# BMS_Carrier_-_Connectors.net
KiCad netlist of a schematic drawn in Altium Designer
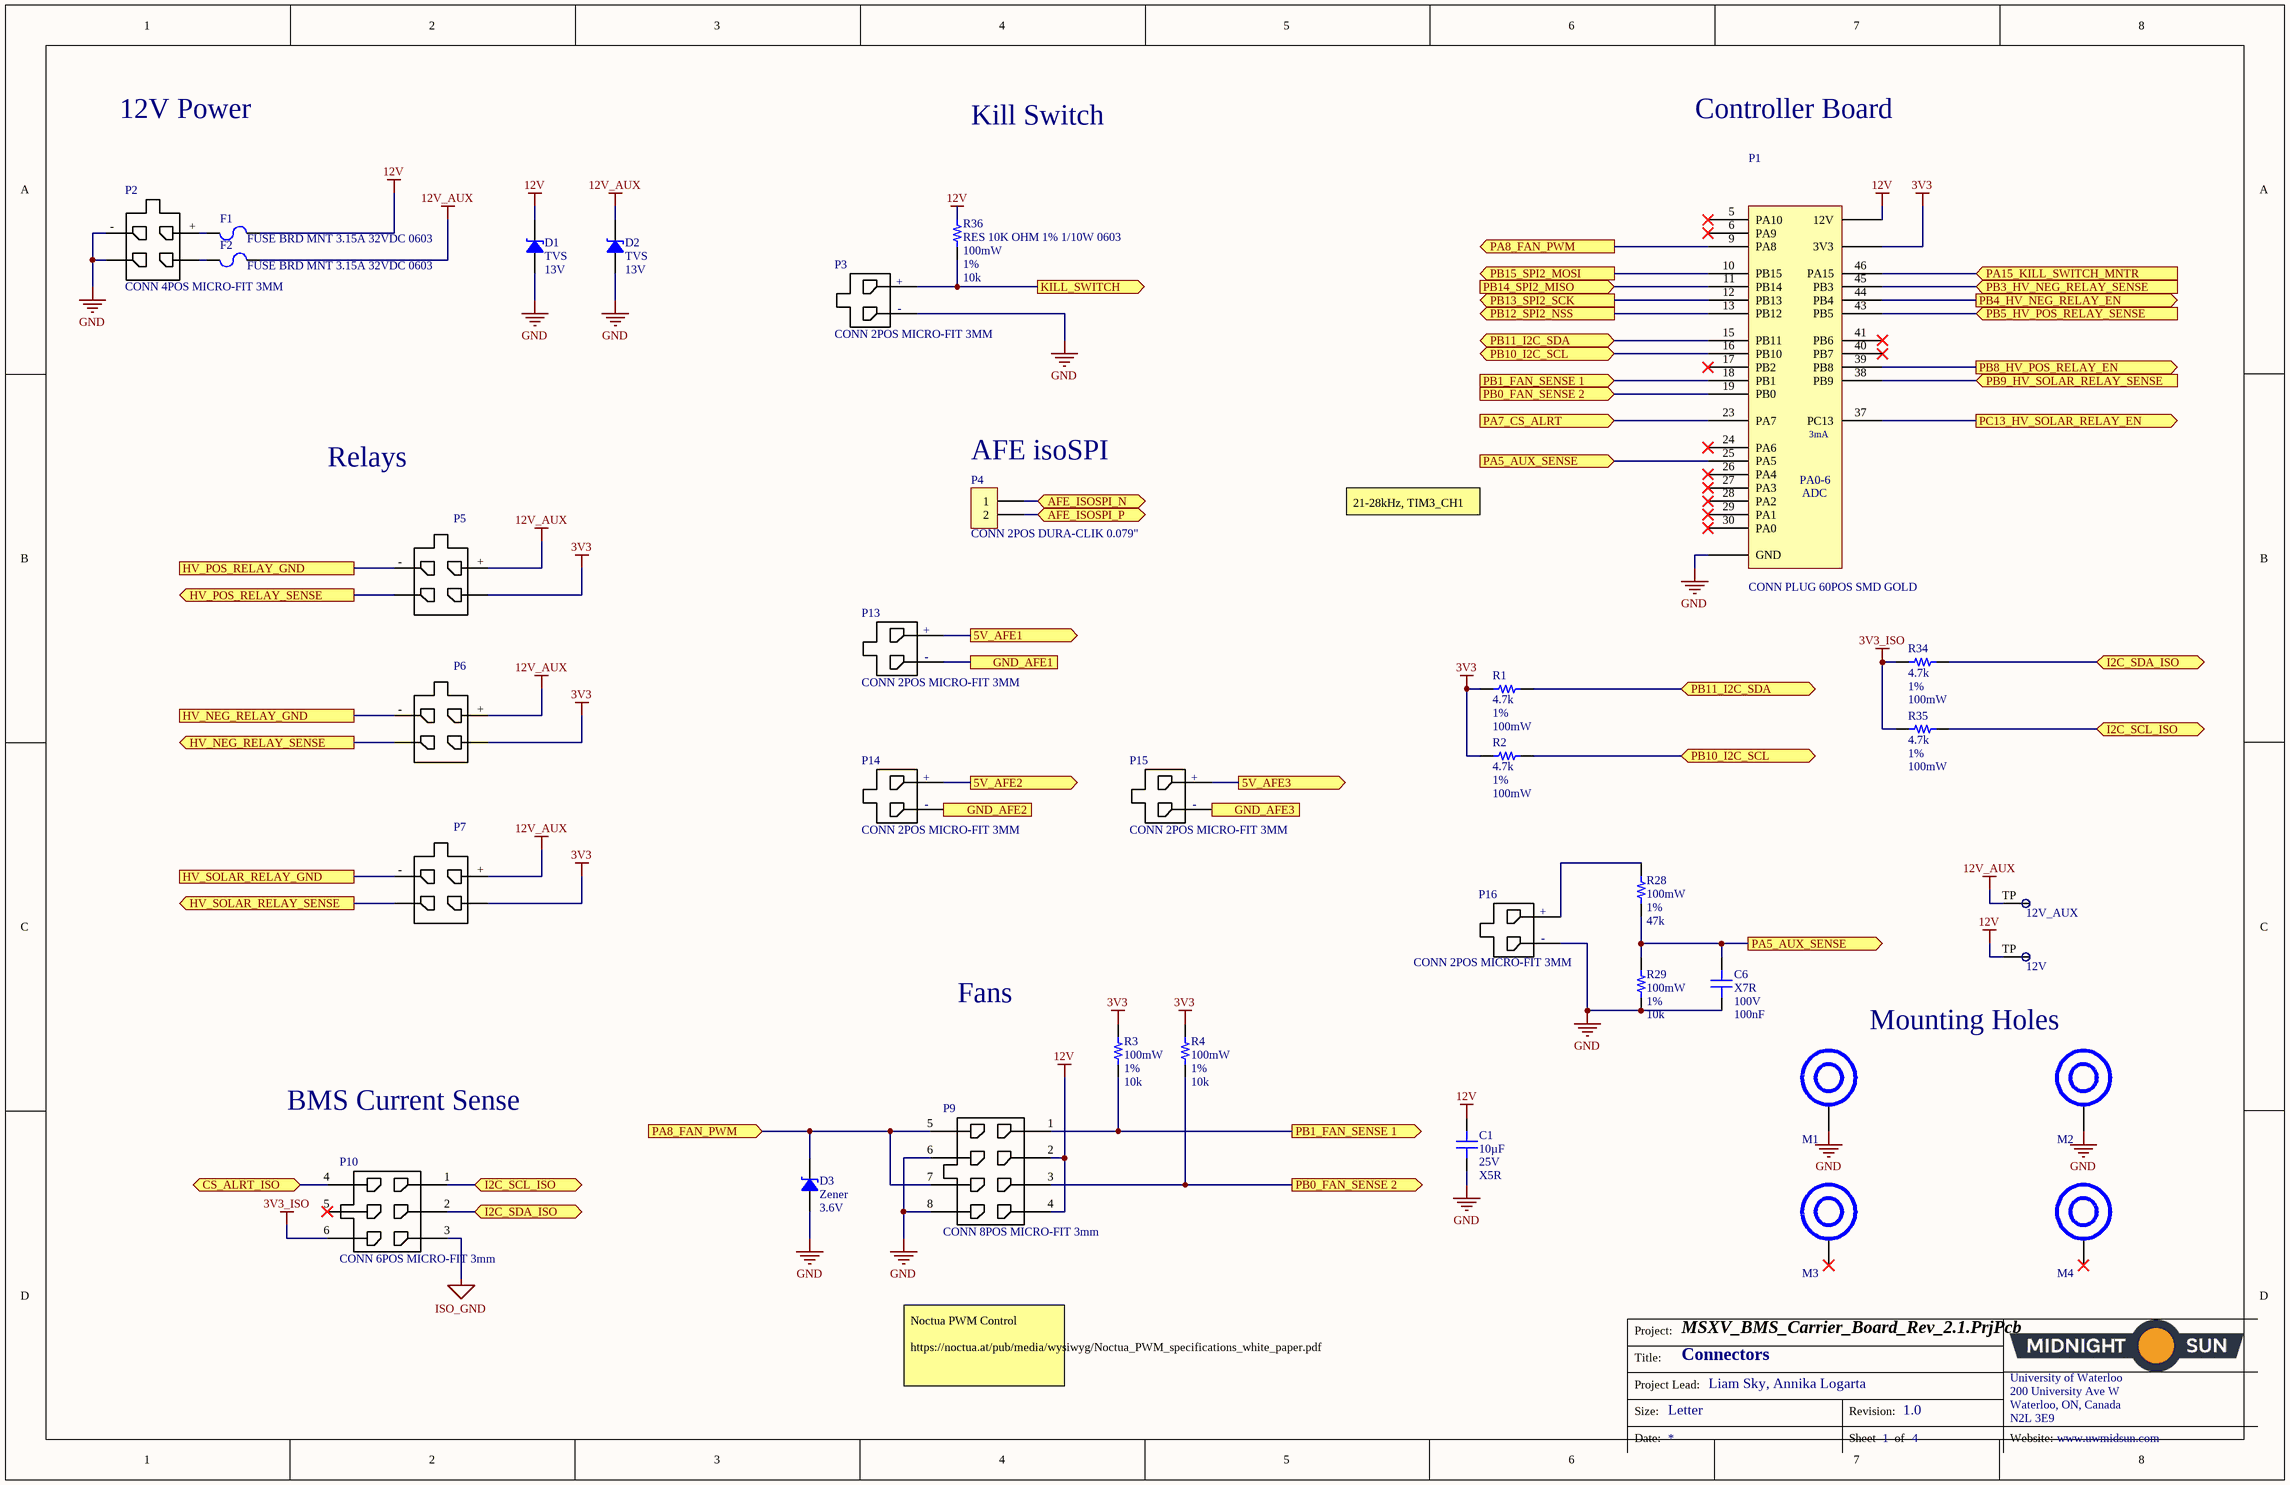
[diagram p0: BMS Carrier - Connectors.SchDoc]

(export (version "E")
  (design (tool "Eeschema 10.0.6"))
  (components
    (comp (ref "12V")
      (value "Thru Test Point Top")
      (footprint "Thru Test Point Top")
      (description "Through Hole Test Point Top Layer")
      (libsource (lib "Midnight Sun") (part "Test Point"))
    )
    (comp (ref "12V_AUX")
      (value "Thru Test Point Top")
      (footprint "Thru Test Point Top")
      (description "Through Hole Test Point Top Layer")
      (libsource (lib "Midnight Sun") (part "Test Point"))
    )
    (comp (ref "C1")
      (value "CAP CER 10UF 25V 20% X5R 0603")
      (footprint "CAP 0603_1608")
      (description "10µF ±20% 25V Ceramic Capacitor X5R 0603 (1608 Metric)")
      (fields
        (field (name "TOLERANCE") "20%")
        (field (name "CAPACITANCE") "10µF")
        (field (name "VOLTAGE RATING") "25V")
        (field (name "DIELECTRIC CODE") "X5R")
      )
      (libsource (lib "Midnight Sun") (part "Capacitor"))
    )
    (comp (ref "C6")
      (value "CAP CER 0.1UF 100V 10% X7R 0603")
      (footprint "CAP 0603_1608")
      (fields
        (field (name "DIELECTRIC CODE") "X7R")
        (field (name "VOLTAGE RATING") "100V")
        (field (name "CAPACITANCE") "100nF")
        (field (name "TOLERANCE") "10%")
      )
      (libsource (lib "Midnight Sun") (part "Capacitor"))
    )
    (comp (ref "D1")
      (value "TVS DIODE 13VWM 21.5VC SMB")
      (footprint "DO 214AC SMA")
      (description "Trans Voltage Suppressor Diode, 600W, 13V V(RWM), Bidirectional, 1 Element, Silicon")
      (fields (field (name "TYPE") "TVS") (field (name "REVERSE BLOCKING VOLTAGE") "13V"))
      (libsource (lib "Midnight Sun") (part "Diode Zener/TVS"))
    )
    (comp (ref "D2")
      (value "TVS DIODE 13VWM 21.5VC SMB")
      (footprint "DO 214AC SMA")
      (description "Trans Voltage Suppressor Diode, 600W, 13V V(RWM), Bidirectional, 1 Element, Silicon")
      (fields (field (name "TYPE") "TVS") (field (name "REVERSE BLOCKING VOLTAGE") "13V"))
      (libsource (lib "Midnight Sun") (part "Diode Zener/TVS"))
    )
    (comp (ref "D3")
      (value "DIODE ZENER 3.6V 300MW SOD323")
      (footprint "SOD 323")
      (description "Zener Diode, 3.6V V(Z), 5.56%, 0.3W, Silicon, Unidirectional")
      (fields (field (name "TYPE") "Zener") (field (name "BREAKDOWN VOLTAGE") "3.6V"))
      (libsource (lib "Midnight Sun") (part "Diode Zener/TVS"))
    )
    (comp (ref "F1")
      (value "FUSE BRD MNT 3.15A 32VDC 0603")
      (footprint "FER 0603_1608")
      (description "Electric Fuse, Very Fast Blow, 3.15A, 32VDC, 50A (IR), Surface Mount")
      (libsource (lib "Midnight Sun") (part "MOUNTED FUSE"))
    )
    (comp (ref "F2")
      (value "FUSE BRD MNT 3.15A 32VDC 0603")
      (footprint "FER 0603_1608")
      (description "Electric Fuse, Very Fast Blow, 3.15A, 32VDC, 50A (IR), Surface Mount")
      (libsource (lib "Midnight Sun") (part "MOUNTED FUSE"))
    )
    (comp (ref "M1")
      (value "HEX STANDOFF M2.5X0.45 BRASS 5MM")
      (footprint "HEX STANDOFF M2.5X0.45 BRASS 5MM-Footprint-1")
      (description "Hex Standoff Threaded M2.5x0.45 Brass 0.197\" (5.00mm)")
      (libsource (lib "Midnight Sun") (part "HEX STANDOFF M2.5X0.45 5MM"))
    )
    (comp (ref "M2")
      (value "HEX STANDOFF M2.5X0.45 BRASS 5MM")
      (footprint "HEX STANDOFF M2.5X0.45 BRASS 5MM-Footprint-1")
      (description "Hex Standoff Threaded M2.5x0.45 Brass 0.197\" (5.00mm)")
      (libsource (lib "Midnight Sun") (part "HEX STANDOFF M2.5X0.45 5MM"))
    )
    (comp (ref "M3")
      (value "HEX STANDOFF M2.5X0.45 BRASS 5MM")
      (footprint "HEX STANDOFF M2.5X0.45 BRASS 5MM-Footprint-1")
      (description "Hex Standoff Threaded M2.5x0.45 Brass 0.197\" (5.00mm)")
      (libsource (lib "Midnight Sun") (part "HEX STANDOFF M2.5X0.45 5MM"))
    )
    (comp (ref "M4")
      (value "HEX STANDOFF M2.5X0.45 BRASS 5MM")
      (footprint "HEX STANDOFF M2.5X0.45 BRASS 5MM-Footprint-1")
      (description "Hex Standoff Threaded M2.5x0.45 Brass 0.197\" (5.00mm)")
      (libsource (lib "Midnight Sun") (part "HEX STANDOFF M2.5X0.45 5MM"))
    )
    (comp (ref "P1")
      (value "CONN PLUG 60POS SMD GOLD")
      (footprint "CONN PLUG 60POS SMD GOLD-CONTROLLER BOARD")
      (description "Height Rec CONNECTOR-10132798-062100LF / 4800 Rohs Compliant: Yes")
      (libsource (lib "Midnight Sun") (part "CONN PLUG 60POS SMD GOLD-Symbol-1"))
    )
    (comp (ref "P2")
      (value "CONN 4POS MICRO-FIT 3MM")
      (footprint "CONN 4POS MICROFIT (2x2)")
      (description "Rectangular Power Connector, 4 Contact(s), Male, Solder Terminal, Plug")
      (libsource (lib "Midnight Sun") (part "CONN 4POS MICRO-FIT 3mm"))
    )
    (comp (ref "P3")
      (value "CONN 2POS MICRO-FIT 3MM")
      (footprint "2POS Molex Microfit 3mm Vert")
      (description "Connector Header Through Hole 2 position 0.118\" (3.00mm)")
      (libsource (lib "Midnight Sun") (part "43650-0227-Symbol-1"))
    )
    (comp (ref "P4")
      (value "CONN 2POS DURA-CLIK 0.079\"")
      (footprint "CONN, 2POS Dura-Click")
      (description "2 Positions Header, Shrouded Connector 0.079\" (2.00mm) Surface Mount, Right Angle Tin")
      (libsource (lib "Midnight Sun") (part "Symbol"))
    )
    (comp (ref "P5")
      (value "CONN 4POS MICRO-FIT 3MM")
      (footprint "CONN 4POS MICROFIT (2x2)")
      (description "Rectangular Power Connector, 4 Contact(s), Male, Solder Terminal, Plug")
      (libsource (lib "Midnight Sun") (part "CONN 4POS MICRO-FIT 3mm"))
    )
    (comp (ref "P6")
      (value "CONN 4POS MICRO-FIT 3MM")
      (footprint "CONN 4POS MICROFIT (2x2)")
      (description "Rectangular Power Connector, 4 Contact(s), Male, Solder Terminal, Plug")
      (libsource (lib "Midnight Sun") (part "CONN 4POS MICRO-FIT 3mm"))
    )
    (comp (ref "P7")
      (value "CONN 4POS MICRO-FIT 3MM")
      (footprint "CONN 4POS MICROFIT (2x2)")
      (description "Rectangular Power Connector, 4 Contact(s), Male, Solder Terminal, Plug")
      (libsource (lib "Midnight Sun") (part "CONN 4POS MICRO-FIT 3mm"))
    )
    (comp (ref "P9")
      (value "CONN 8POS MICRO-FIT 3mm")
      (footprint "CONN, 8POS MICRO-FIT")
      (description "Connector Header Through Hole 6 position 0.118\" (3.00mm)")
      (libsource (lib "Midnight Sun") (part "CONN 8POS MICRO-FIT 3mm"))
    )
    (comp (ref "P10")
      (value "CONN 6POS MICRO-FIT 3mm")
      (footprint "CONN, 6POS MICRO-FIT 3MM")
      (description "Connector Header Through Hole 6 position 0.118\" (3.00mm)")
      (libsource (lib "Midnight Sun") (part "CONN 6POS MICRO-FIT 3mm"))
    )
    (comp (ref "P13")
      (value "CONN 2POS MICRO-FIT 3MM")
      (footprint "2POS Molex Microfit 3mm Vert")
      (description "Connector Header Through Hole 2 position 0.118\" (3.00mm)")
      (libsource (lib "Midnight Sun") (part "43650-0227-Symbol-1"))
    )
    (comp (ref "P14")
      (value "CONN 2POS MICRO-FIT 3MM")
      (footprint "2POS Molex Microfit 3mm Vert")
      (description "Connector Header Through Hole 2 position 0.118\" (3.00mm)")
      (libsource (lib "Midnight Sun") (part "43650-0227-Symbol-1"))
    )
    (comp (ref "P15")
      (value "CONN 2POS MICRO-FIT 3MM")
      (footprint "2POS Molex Microfit 3mm Vert")
      (description "Connector Header Through Hole 2 position 0.118\" (3.00mm)")
      (libsource (lib "Midnight Sun") (part "43650-0227-Symbol-1"))
    )
    (comp (ref "P16")
      (value "CONN 2POS MICRO-FIT 3MM")
      (footprint "2POS Molex Microfit 3mm Vert")
      (description "Connector Header Through Hole 2 position 0.118\" (3.00mm)")
      (libsource (lib "Midnight Sun") (part "43650-0227-Symbol-1"))
    )
    (comp (ref "R1")
      (value "RES 4.7K OHM 1% 1/10W 0603")
      (footprint "RES 0603_1608")
      (fields
        (field (name "RESISTANCE") "4.7k")
        (field (name "TOLERANCE") "1%")
        (field (name "POWER RATING") "100mW")
      )
      (libsource (lib "Midnight Sun") (part "Resistor"))
    )
    (comp (ref "R2")
      (value "RES 4.7K OHM 1% 1/10W 0603")
      (footprint "RES 0603_1608")
      (fields
        (field (name "RESISTANCE") "4.7k")
        (field (name "TOLERANCE") "1%")
        (field (name "POWER RATING") "100mW")
      )
      (libsource (lib "Midnight Sun") (part "Resistor"))
    )
    (comp (ref "R3")
      (value "RES 10K OHM 1% 1/10W 0603")
      (footprint "RES 0603_1608")
      (description "10 ±1% 0.1W, 1/10W Chip Resistor 0603 (1608 Metric) Automotive AEC-Q200 Thick Film")
      (fields
        (field (name "POWER RATING") "100mW")
        (field (name "TOLERANCE") "1%")
        (field (name "RESISTANCE") "10k")
      )
      (libsource (lib "Midnight Sun") (part "Resistor"))
    )
    (comp (ref "R4")
      (value "RES 10K OHM 1% 1/10W 0603")
      (footprint "RES 0603_1608")
      (description "10 ±1% 0.1W, 1/10W Chip Resistor 0603 (1608 Metric) Automotive AEC-Q200 Thick Film")
      (fields
        (field (name "POWER RATING") "100mW")
        (field (name "TOLERANCE") "1%")
        (field (name "RESISTANCE") "10k")
      )
      (libsource (lib "Midnight Sun") (part "Resistor"))
    )
    (comp (ref "R28")
      (value "RES 47K OHM 1% 1/10W 0603")
      (footprint "RES 0603_1608")
      (fields
        (field (name "POWER RATING") "100mW")
        (field (name "TOLERANCE") "1%")
        (field (name "RESISTANCE") "47k")
      )
      (libsource (lib "Midnight Sun") (part "Resistor"))
    )
    (comp (ref "R29")
      (value "RES 10K OHM 1% 1/10W 0603")
      (footprint "RES 0603_1608")
      (description "10 ±1% 0.1W, 1/10W Chip Resistor 0603 (1608 Metric) Automotive AEC-Q200 Thick Film")
      (fields
        (field (name "POWER RATING") "100mW")
        (field (name "TOLERANCE") "1%")
        (field (name "RESISTANCE") "10k")
      )
      (libsource (lib "Midnight Sun") (part "Resistor"))
    )
    (comp (ref "R34")
      (value "RES 4.7K OHM 1% 1/10W 0603")
      (footprint "RES 0603_1608")
      (fields
        (field (name "RESISTANCE") "4.7k")
        (field (name "TOLERANCE") "1%")
        (field (name "POWER RATING") "100mW")
      )
      (libsource (lib "Midnight Sun") (part "Resistor"))
    )
    (comp (ref "R35")
      (value "RES 4.7K OHM 1% 1/10W 0603")
      (footprint "RES 0603_1608")
      (fields
        (field (name "RESISTANCE") "4.7k")
        (field (name "TOLERANCE") "1%")
        (field (name "POWER RATING") "100mW")
      )
      (libsource (lib "Midnight Sun") (part "Resistor"))
    )
    (comp (ref "R36")
      (value "RES 10K OHM 1% 1/10W 0603")
      (footprint "RES 0603_1608")
      (description "10 ±1% 0.1W, 1/10W Chip Resistor 0603 (1608 Metric) Automotive AEC-Q200 Thick Film")
      (fields
        (field (name "POWER RATING") "100mW")
        (field (name "TOLERANCE") "1%")
        (field (name "RESISTANCE") "10k")
      )
      (libsource (lib "Midnight Sun") (part "Resistor"))
    )
  )
  (nets
    (net (code "1") (name "/5V_AFE1") (class "Default")
      (node (ref "P13") (pin "1") (pinfunction "VCC_1") (pintype "passive"))
    )
    (net (code "2") (name "/5V_AFE2") (class "Default")
      (node (ref "P14") (pin "1") (pinfunction "VCC_1") (pintype "passive"))
    )
    (net (code "3") (name "/5V_AFE3") (class "Default")
      (node (ref "P15") (pin "1") (pinfunction "VCC_1") (pintype "passive"))
    )
    (net (code "4") (name "/AFE_ISOSPI_N") (class "Default")
      (node (ref "P4") (pin "1") (pinfunction "1_1") (pintype "passive"))
    )
    (net (code "5") (name "/AFE_ISOSPI_P") (class "Default")
      (node (ref "P4") (pin "2") (pinfunction "2_2") (pintype "passive"))
    )
    (net (code "6") (name "/CS_ALRT_ISO") (class "Default")
      (node (ref "P10") (pin "4") (pinfunction "4_4") (pintype "passive"))
    )
    (net (code "7") (name "/GND_AFE1") (class "Default")
      (node (ref "P13") (pin "2") (pinfunction "GND_2") (pintype "passive"))
    )
    (net (code "8") (name "/GND_AFE2") (class "Default")
      (node (ref "P14") (pin "2") (pinfunction "GND_2") (pintype "passive"))
    )
    (net (code "9") (name "/GND_AFE3") (class "Default")
      (node (ref "P15") (pin "2") (pinfunction "GND_2") (pintype "passive"))
    )
    (net (code "10") (name "/HV_NEG_RELAY_GND") (class "Default")
      (node (ref "P6") (pin "4") (pinfunction "-_4") (pintype "passive"))
    )
    (net (code "11") (name "/HV_NEG_RELAY_SENSE") (class "Default")
      (node (ref "P6") (pin "2") (pinfunction "2_2") (pintype "passive"))
    )
    (net (code "12") (name "/HV_POS_RELAY_GND") (class "Default")
      (node (ref "P5") (pin "4") (pinfunction "-_4") (pintype "passive"))
    )
    (net (code "13") (name "/HV_POS_RELAY_SENSE") (class "Default")
      (node (ref "P5") (pin "2") (pinfunction "2_2") (pintype "passive"))
    )
    (net (code "14") (name "/HV_SOLAR_RELAY_GND") (class "Default")
      (node (ref "P7") (pin "4") (pinfunction "-_4") (pintype "passive"))
    )
    (net (code "15") (name "/HV_SOLAR_RELAY_SENSE") (class "Default")
      (node (ref "P7") (pin "2") (pinfunction "2_2") (pintype "passive"))
    )
    (net (code "16") (name "/I2C_SCL_ISO") (class "Default")
      (node (ref "P10") (pin "1") (pinfunction "1_1") (pintype "passive"))
      (node (ref "R35") (pin "1") (pinfunction "1_1") (pintype "passive"))
    )
    (net (code "17") (name "/I2C_SDA_ISO") (class "Default")
      (node (ref "P10") (pin "2") (pinfunction "2_2") (pintype "passive"))
      (node (ref "R34") (pin "1") (pinfunction "1_1") (pintype "passive"))
    )
    (net (code "18") (name "/KILL_SWITCH") (class "Default")
      (node (ref "P3") (pin "1") (pinfunction "VCC_1") (pintype "passive"))
      (node (ref "R36") (pin "1") (pinfunction "1_1") (pintype "passive"))
    )
    (net (code "19") (name "/PA5_AUX_SENSE") (class "Default")
      (node (ref "C6") (pin "1") (pinfunction "1_1") (pintype "passive"))
      (node (ref "P1") (pin "25") (pinfunction "PA5_25") (pintype "passive"))
      (node (ref "R28") (pin "1") (pinfunction "1_1") (pintype "passive"))
      (node (ref "R29") (pin "2") (pinfunction "2_2") (pintype "passive"))
    )
    (net (code "20") (name "/PA7_CS_ALRT") (class "Default")
      (node (ref "P1") (pin "23") (pinfunction "PA7_23") (pintype "passive"))
    )
    (net (code "21") (name "/PA8_FAN_PWM") (class "Default")
      (node (ref "D3") (pin "1") (pinfunction "1_1") (pintype "passive"))
      (node (ref "P1") (pin "9") (pinfunction "PA8_9") (pintype "passive"))
      (node (ref "P9") (pin "5") (pinfunction "5_5") (pintype "passive"))
      (node (ref "P9") (pin "7") (pinfunction "7_7") (pintype "passive"))
    )
    (net (code "22") (name "/PA15_KILL_SWITCH_MNTR") (class "Default")
      (node (ref "P1") (pin "46") (pinfunction "PA15_46") (pintype "passive"))
    )
    (net (code "23") (name "/PB0_FAN_SENSE 2") (class "Default")
      (node (ref "P1") (pin "19") (pinfunction "PB0_19") (pintype "passive"))
      (node (ref "P9") (pin "3") (pinfunction "3_3") (pintype "passive"))
      (node (ref "R4") (pin "1") (pinfunction "1_1") (pintype "passive"))
    )
    (net (code "24") (name "/PB1_FAN_SENSE 1") (class "Default")
      (node (ref "P1") (pin "18") (pinfunction "PB1_18") (pintype "passive"))
      (node (ref "P9") (pin "1") (pinfunction "1_1") (pintype "passive"))
      (node (ref "R3") (pin "1") (pinfunction "1_1") (pintype "passive"))
    )
    (net (code "25") (name "/PB3_HV_NEG_RELAY_SENSE") (class "Default")
      (node (ref "P1") (pin "45") (pinfunction "PB3_45") (pintype "passive"))
    )
    (net (code "26") (name "/PB4_HV_NEG_RELAY_EN") (class "Default")
      (node (ref "P1") (pin "44") (pinfunction "PB4_44") (pintype "passive"))
    )
    (net (code "27") (name "/PB5_HV_POS_RELAY_SENSE") (class "Default")
      (node (ref "P1") (pin "43") (pinfunction "PB5_43") (pintype "passive"))
    )
    (net (code "28") (name "/PB8_HV_POS_RELAY_EN") (class "Default")
      (node (ref "P1") (pin "39") (pinfunction "PB8_39") (pintype "passive"))
    )
    (net (code "29") (name "/PB9_HV_SOLAR_RELAY_SENSE") (class "Default")
      (node (ref "P1") (pin "38") (pinfunction "PB9_38") (pintype "passive"))
    )
    (net (code "30") (name "/PB10_I2C_SCL") (class "Default")
      (node (ref "P1") (pin "16") (pinfunction "PB10_16") (pintype "passive"))
      (node (ref "R2") (pin "1") (pinfunction "1_1") (pintype "passive"))
    )
    (net (code "31") (name "/PB11_I2C_SDA") (class "Default")
      (node (ref "P1") (pin "15") (pinfunction "PB11_15") (pintype "passive"))
      (node (ref "R1") (pin "1") (pinfunction "1_1") (pintype "passive"))
    )
    (net (code "32") (name "/PB12_SPI2_NSS") (class "Default")
      (node (ref "P1") (pin "13") (pinfunction "PB12_13") (pintype "passive"))
    )
    (net (code "33") (name "/PB13_SPI2_SCK") (class "Default")
      (node (ref "P1") (pin "12") (pinfunction "PB13_12") (pintype "passive"))
    )
    (net (code "34") (name "/PB14_SPI2_MISO") (class "Default")
      (node (ref "P1") (pin "11") (pinfunction "PB14_11") (pintype "passive"))
    )
    (net (code "35") (name "/PB15_SPI2_MOSI") (class "Default")
      (node (ref "P1") (pin "10") (pinfunction "PB15_10") (pintype "passive"))
    )
    (net (code "36") (name "/PC13_HV_SOLAR_RELAY_EN") (class "Default")
      (node (ref "P1") (pin "37") (pinfunction "PC13_37") (pintype "passive"))
    )
    (net (code "37") (name "3V3") (class "Default")
      (node (ref "P1") (pin "53") (pinfunction "3V3_53") (pintype "power_in"))
      (node (ref "P5") (pin "1") (pinfunction "1_1") (pintype "passive"))
      (node (ref "P6") (pin "1") (pinfunction "1_1") (pintype "passive"))
      (node (ref "P7") (pin "1") (pinfunction "1_1") (pintype "passive"))
      (node (ref "R1") (pin "2") (pinfunction "2_2") (pintype "passive"))
      (node (ref "R2") (pin "2") (pinfunction "2_2") (pintype "passive"))
      (node (ref "R3") (pin "2") (pinfunction "2_2") (pintype "passive"))
      (node (ref "R4") (pin "2") (pinfunction "2_2") (pintype "passive"))
    )
    (net (code "38") (name "3V3_ISO") (class "Default")
      (node (ref "P10") (pin "6") (pinfunction "6_6") (pintype "passive"))
      (node (ref "R34") (pin "2") (pinfunction "2_2") (pintype "passive"))
      (node (ref "R35") (pin "2") (pinfunction "2_2") (pintype "passive"))
    )
    (net (code "39") (name "12V") (class "Default")
      (node (ref "12V") (pin "TP") (pinfunction "1_TP") (pintype "passive"))
      (node (ref "C1") (pin "2") (pinfunction "2_2") (pintype "passive"))
      (node (ref "D1") (pin "1") (pinfunction "1_1") (pintype "passive"))
      (node (ref "F1") (pin "1") (pinfunction "1_1") (pintype "passive"))
      (node (ref "P1") (pin "60") (pinfunction "12V_60") (pintype "power_in"))
      (node (ref "P9") (pin "2") (pinfunction "2_2") (pintype "passive"))
      (node (ref "P9") (pin "4") (pinfunction "4_4") (pintype "passive"))
      (node (ref "R36") (pin "2") (pinfunction "2_2") (pintype "passive"))
    )
    (net (code "40") (name "12V_AUX") (class "Default")
      (node (ref "12V_AUX") (pin "TP") (pinfunction "1_TP") (pintype "passive"))
      (node (ref "D2") (pin "1") (pinfunction "1_1") (pintype "passive"))
      (node (ref "F2") (pin "1") (pinfunction "1_1") (pintype "passive"))
      (node (ref "P5") (pin "3") (pinfunction "+_3") (pintype "passive"))
      (node (ref "P6") (pin "3") (pinfunction "+_3") (pintype "passive"))
      (node (ref "P7") (pin "3") (pinfunction "+_3") (pintype "passive"))
    )
    (net (code "41") (name "GND") (class "Default")
      (node (ref "C1") (pin "1") (pinfunction "1_1") (pintype "passive"))
      (node (ref "C6") (pin "2") (pinfunction "2_2") (pintype "passive"))
      (node (ref "D1") (pin "2") (pinfunction "2_2") (pintype "passive"))
      (node (ref "D2") (pin "2") (pinfunction "2_2") (pintype "passive"))
      (node (ref "D3") (pin "2") (pinfunction "2_2") (pintype "passive"))
      (node (ref "M1") (pin "0") (pinfunction "0_0") (pintype "passive"))
      (node (ref "M2") (pin "0") (pinfunction "0_0") (pintype "passive"))
      (node (ref "P1") (pin "31") (pinfunction "GND_31") (pintype "passive"))
      (node (ref "P16") (pin "2") (pinfunction "GND_2") (pintype "passive"))
      (node (ref "P2") (pin "2") (pinfunction "2_2") (pintype "passive"))
      (node (ref "P2") (pin "4") (pinfunction "-_4") (pintype "passive"))
      (node (ref "P3") (pin "2") (pinfunction "GND_2") (pintype "passive"))
      (node (ref "P9") (pin "6") (pinfunction "6_6") (pintype "passive"))
      (node (ref "P9") (pin "8") (pinfunction "8_8") (pintype "passive"))
      (node (ref "R29") (pin "1") (pinfunction "1_1") (pintype "passive"))
    )
    (net (code "42") (name "ISO_GND") (class "Default")
      (node (ref "P10") (pin "3") (pinfunction "3_3") (pintype "passive"))
    )
    (net (code "43") (name "Net-(F2-Pad2)") (class "Default")
      (node (ref "F2") (pin "2") (pinfunction "2_2") (pintype "passive"))
      (node (ref "P2") (pin "1") (pinfunction "1_1") (pintype "passive"))
    )
    (net (code "44") (name "Net-(P2-+)") (class "Default")
      (node (ref "F1") (pin "2") (pinfunction "2_2") (pintype "passive"))
      (node (ref "P2") (pin "3") (pinfunction "+_3") (pintype "passive"))
    )
    (net (code "45") (name "Net-(P16-VCC)") (class "Default")
      (node (ref "P16") (pin "1") (pinfunction "VCC_1") (pintype "passive"))
      (node (ref "R28") (pin "2") (pinfunction "2_2") (pintype "passive"))
    )
    (net (code "46") (name "unconnected-(M3-Pad0)") (class "Default")
      (node (ref "M3") (pin "0") (pinfunction "0_0") (pintype "passive+no_connect"))
    )
    (net (code "47") (name "unconnected-(M4-Pad0)") (class "Default")
      (node (ref "M4") (pin "0") (pinfunction "0_0") (pintype "passive+no_connect"))
    )
    (net (code "48") (name "unconnected-(P1-PA0-Pad30)") (class "Default")
      (node (ref "P1") (pin "30") (pinfunction "PA0_30") (pintype "passive+no_connect"))
    )
    (net (code "49") (name "unconnected-(P1-PA1-Pad29)") (class "Default")
      (node (ref "P1") (pin "29") (pinfunction "PA1_29") (pintype "passive+no_connect"))
    )
    (net (code "50") (name "unconnected-(P1-PA2-Pad28)") (class "Default")
      (node (ref "P1") (pin "28") (pinfunction "PA2_28") (pintype "passive+no_connect"))
    )
    (net (code "51") (name "unconnected-(P1-PA3-Pad27)") (class "Default")
      (node (ref "P1") (pin "27") (pinfunction "PA3_27") (pintype "passive+no_connect"))
    )
    (net (code "52") (name "unconnected-(P1-PA4-Pad26)") (class "Default")
      (node (ref "P1") (pin "26") (pinfunction "PA4_26") (pintype "passive+no_connect"))
    )
    (net (code "53") (name "unconnected-(P1-PA6-Pad24)") (class "Default")
      (node (ref "P1") (pin "24") (pinfunction "PA6_24") (pintype "passive+no_connect"))
    )
    (net (code "54") (name "unconnected-(P1-PA9-Pad6)") (class "Default")
      (node (ref "P1") (pin "6") (pinfunction "PA9_6") (pintype "passive+no_connect"))
    )
    (net (code "55") (name "unconnected-(P1-PA10-Pad5)") (class "Default")
      (node (ref "P1") (pin "5") (pinfunction "PA10_5") (pintype "passive+no_connect"))
    )
    (net (code "56") (name "unconnected-(P1-PB2-Pad17)") (class "Default")
      (node (ref "P1") (pin "17") (pinfunction "PB2_17") (pintype "passive+no_connect"))
    )
    (net (code "57") (name "unconnected-(P1-PB6-Pad41)") (class "Default")
      (node (ref "P1") (pin "41") (pinfunction "PB6_41") (pintype "passive+no_connect"))
    )
    (net (code "58") (name "unconnected-(P1-PB7-Pad40)") (class "Default")
      (node (ref "P1") (pin "40") (pinfunction "PB7_40") (pintype "passive+no_connect"))
    )
    (net (code "59") (name "unconnected-(P10-Pad5)") (class "Default")
      (node (ref "P10") (pin "5") (pinfunction "5_5") (pintype "passive+no_connect"))
    )
  )
)
